# converter.net
KiCad netlist of a schematic drawn in EAGLE
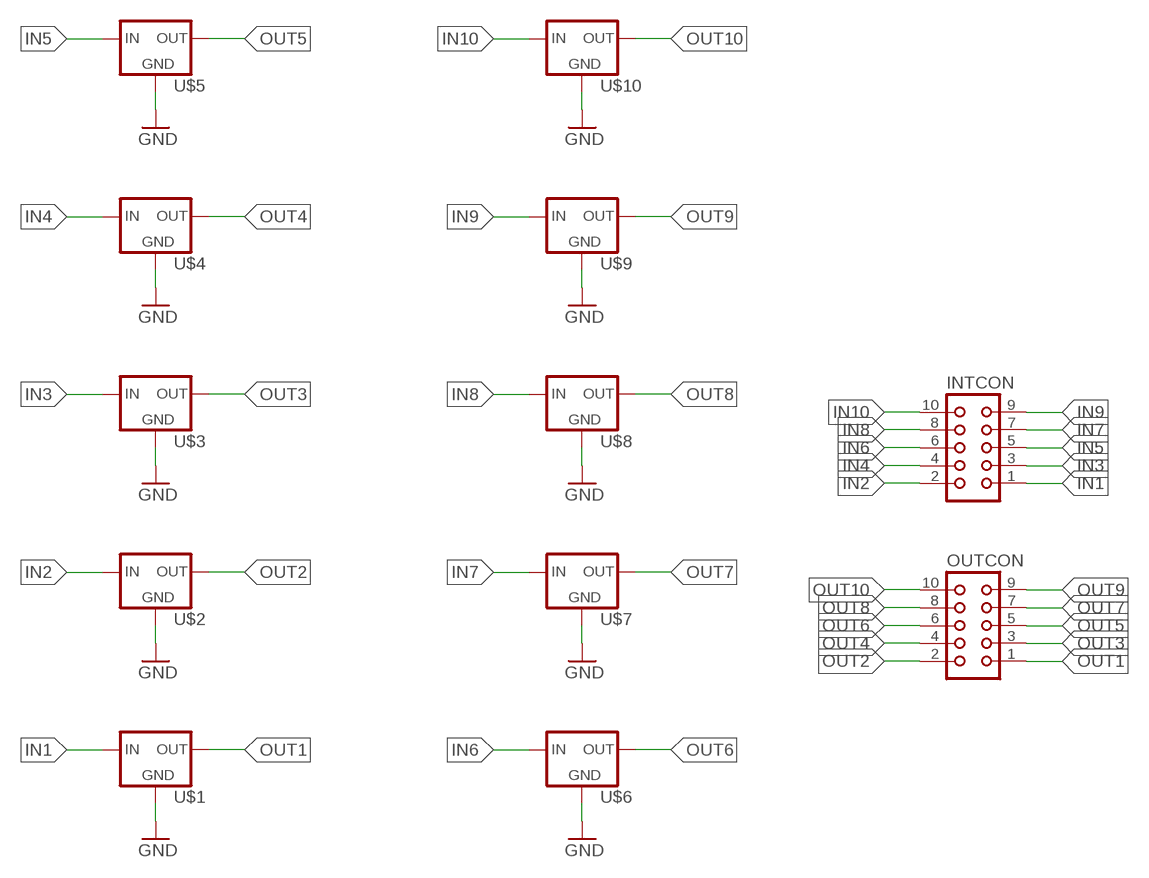
[diagram p0: schematic, sheet 1]

(export (version "E")
  (design (tool "Eeschema 10.0.6"))
  (components
    (comp (ref "INTCON")
      (value "CON10")
      (footprint "eagle-import:CON10")
      (libsource (lib "eagle-import") (part "CON10"))
    )
    (comp (ref "OUTCON")
      (value "CON10")
      (footprint "eagle-import:CON10")
      (libsource (lib "eagle-import") (part "CON10"))
    )
    (comp (ref "U$1")
      (value "LOGIC_CONVERTERIC")
      (footprint "eagle-import:SOT223")
      (libsource (lib "eagle-import") (part "LOGIC_CONVERTERIC"))
    )
    (comp (ref "U$2")
      (value "LOGIC_CONVERTERIC")
      (footprint "eagle-import:SOT223")
      (libsource (lib "eagle-import") (part "LOGIC_CONVERTERIC"))
    )
    (comp (ref "U$3")
      (value "LOGIC_CONVERTERIC")
      (footprint "eagle-import:SOT223")
      (libsource (lib "eagle-import") (part "LOGIC_CONVERTERIC"))
    )
    (comp (ref "U$4")
      (value "LOGIC_CONVERTERIC")
      (footprint "eagle-import:SOT223")
      (libsource (lib "eagle-import") (part "LOGIC_CONVERTERIC"))
    )
    (comp (ref "U$5")
      (value "LOGIC_CONVERTERIC")
      (footprint "eagle-import:SOT223")
      (libsource (lib "eagle-import") (part "LOGIC_CONVERTERIC"))
    )
    (comp (ref "U$6")
      (value "LOGIC_CONVERTERIC")
      (footprint "eagle-import:SOT223")
      (libsource (lib "eagle-import") (part "LOGIC_CONVERTERIC"))
    )
    (comp (ref "U$7")
      (value "LOGIC_CONVERTERIC")
      (footprint "eagle-import:SOT223")
      (libsource (lib "eagle-import") (part "LOGIC_CONVERTERIC"))
    )
    (comp (ref "U$8")
      (value "LOGIC_CONVERTERIC")
      (footprint "eagle-import:SOT223")
      (libsource (lib "eagle-import") (part "LOGIC_CONVERTERIC"))
    )
    (comp (ref "U$9")
      (value "LOGIC_CONVERTERIC")
      (footprint "eagle-import:SOT223")
      (libsource (lib "eagle-import") (part "LOGIC_CONVERTERIC"))
    )
    (comp (ref "U$10")
      (value "LOGIC_CONVERTERIC")
      (footprint "eagle-import:SOT223")
      (libsource (lib "eagle-import") (part "LOGIC_CONVERTERIC"))
    )
  )
  (nets
    (net (code "1") (name "GND") (class "Default")
      (node (ref "U$1") (pin "2") (pinfunction "GND_2") (pintype "input"))
      (node (ref "U$1") (pin "3") (pinfunction "GND_3") (pintype "input"))
      (node (ref "U$1") (pin "4") (pinfunction "GND_4") (pintype "input"))
      (node (ref "U$1") (pin "GND") (pinfunction "GND_GND") (pintype "input"))
      (node (ref "U$10") (pin "2") (pinfunction "GND_2") (pintype "input"))
      (node (ref "U$10") (pin "3") (pinfunction "GND_3") (pintype "input"))
      (node (ref "U$10") (pin "4") (pinfunction "GND_4") (pintype "input"))
      (node (ref "U$10") (pin "GND") (pinfunction "GND_GND") (pintype "input"))
      (node (ref "U$2") (pin "2") (pinfunction "GND_2") (pintype "input"))
      (node (ref "U$2") (pin "3") (pinfunction "GND_3") (pintype "input"))
      (node (ref "U$2") (pin "4") (pinfunction "GND_4") (pintype "input"))
      (node (ref "U$2") (pin "GND") (pinfunction "GND_GND") (pintype "input"))
      (node (ref "U$3") (pin "2") (pinfunction "GND_2") (pintype "input"))
      (node (ref "U$3") (pin "3") (pinfunction "GND_3") (pintype "input"))
      (node (ref "U$3") (pin "4") (pinfunction "GND_4") (pintype "input"))
      (node (ref "U$3") (pin "GND") (pinfunction "GND_GND") (pintype "input"))
      (node (ref "U$4") (pin "2") (pinfunction "GND_2") (pintype "input"))
      (node (ref "U$4") (pin "3") (pinfunction "GND_3") (pintype "input"))
      (node (ref "U$4") (pin "4") (pinfunction "GND_4") (pintype "input"))
      (node (ref "U$4") (pin "GND") (pinfunction "GND_GND") (pintype "input"))
      (node (ref "U$5") (pin "2") (pinfunction "GND_2") (pintype "input"))
      (node (ref "U$5") (pin "3") (pinfunction "GND_3") (pintype "input"))
      (node (ref "U$5") (pin "4") (pinfunction "GND_4") (pintype "input"))
      (node (ref "U$5") (pin "GND") (pinfunction "GND_GND") (pintype "input"))
      (node (ref "U$6") (pin "2") (pinfunction "GND_2") (pintype "input"))
      (node (ref "U$6") (pin "3") (pinfunction "GND_3") (pintype "input"))
      (node (ref "U$6") (pin "4") (pinfunction "GND_4") (pintype "input"))
      (node (ref "U$6") (pin "GND") (pinfunction "GND_GND") (pintype "input"))
      (node (ref "U$7") (pin "2") (pinfunction "GND_2") (pintype "input"))
      (node (ref "U$7") (pin "3") (pinfunction "GND_3") (pintype "input"))
      (node (ref "U$7") (pin "4") (pinfunction "GND_4") (pintype "input"))
      (node (ref "U$7") (pin "GND") (pinfunction "GND_GND") (pintype "input"))
      (node (ref "U$8") (pin "2") (pinfunction "GND_2") (pintype "input"))
      (node (ref "U$8") (pin "3") (pinfunction "GND_3") (pintype "input"))
      (node (ref "U$8") (pin "4") (pinfunction "GND_4") (pintype "input"))
      (node (ref "U$8") (pin "GND") (pinfunction "GND_GND") (pintype "input"))
      (node (ref "U$9") (pin "2") (pinfunction "GND_2") (pintype "input"))
      (node (ref "U$9") (pin "3") (pinfunction "GND_3") (pintype "input"))
      (node (ref "U$9") (pin "4") (pinfunction "GND_4") (pintype "input"))
      (node (ref "U$9") (pin "GND") (pinfunction "GND_GND") (pintype "input"))
    )
    (net (code "2") (name "IN1") (class "Default")
      (node (ref "INTCON") (pin "1") (pinfunction "1_1") (pintype "passive"))
      (node (ref "U$1") (pin "1") (pinfunction "IN_1") (pintype "input"))
      (node (ref "U$1") (pin "IN") (pinfunction "IN_IN") (pintype "input"))
    )
    (net (code "3") (name "IN2") (class "Default")
      (node (ref "INTCON") (pin "2") (pinfunction "2_2") (pintype "passive"))
      (node (ref "U$2") (pin "1") (pinfunction "IN_1") (pintype "input"))
      (node (ref "U$2") (pin "IN") (pinfunction "IN_IN") (pintype "input"))
    )
    (net (code "4") (name "IN3") (class "Default")
      (node (ref "INTCON") (pin "3") (pinfunction "3_3") (pintype "passive"))
      (node (ref "U$3") (pin "1") (pinfunction "IN_1") (pintype "input"))
      (node (ref "U$3") (pin "IN") (pinfunction "IN_IN") (pintype "input"))
    )
    (net (code "5") (name "IN4") (class "Default")
      (node (ref "INTCON") (pin "4") (pinfunction "4_4") (pintype "passive"))
      (node (ref "U$4") (pin "1") (pinfunction "IN_1") (pintype "input"))
      (node (ref "U$4") (pin "IN") (pinfunction "IN_IN") (pintype "input"))
    )
    (net (code "6") (name "IN5") (class "Default")
      (node (ref "INTCON") (pin "5") (pinfunction "5_5") (pintype "passive"))
      (node (ref "U$5") (pin "1") (pinfunction "IN_1") (pintype "input"))
      (node (ref "U$5") (pin "IN") (pinfunction "IN_IN") (pintype "input"))
    )
    (net (code "7") (name "IN6") (class "Default")
      (node (ref "INTCON") (pin "6") (pinfunction "6_6") (pintype "passive"))
      (node (ref "U$6") (pin "1") (pinfunction "IN_1") (pintype "input"))
      (node (ref "U$6") (pin "IN") (pinfunction "IN_IN") (pintype "input"))
    )
    (net (code "8") (name "IN7") (class "Default")
      (node (ref "INTCON") (pin "7") (pinfunction "7_7") (pintype "passive"))
      (node (ref "U$7") (pin "1") (pinfunction "IN_1") (pintype "input"))
      (node (ref "U$7") (pin "IN") (pinfunction "IN_IN") (pintype "input"))
    )
    (net (code "9") (name "IN8") (class "Default")
      (node (ref "INTCON") (pin "8") (pinfunction "8_8") (pintype "passive"))
      (node (ref "U$8") (pin "1") (pinfunction "IN_1") (pintype "input"))
      (node (ref "U$8") (pin "IN") (pinfunction "IN_IN") (pintype "input"))
    )
    (net (code "10") (name "IN9") (class "Default")
      (node (ref "INTCON") (pin "9") (pinfunction "9_9") (pintype "passive"))
      (node (ref "U$9") (pin "1") (pinfunction "IN_1") (pintype "input"))
      (node (ref "U$9") (pin "IN") (pinfunction "IN_IN") (pintype "input"))
    )
    (net (code "11") (name "IN10") (class "Default")
      (node (ref "INTCON") (pin "10") (pinfunction "10_10") (pintype "passive"))
      (node (ref "U$10") (pin "1") (pinfunction "IN_1") (pintype "input"))
      (node (ref "U$10") (pin "IN") (pinfunction "IN_IN") (pintype "input"))
    )
    (net (code "12") (name "OUT1") (class "Default")
      (node (ref "OUTCON") (pin "1") (pinfunction "1_1") (pintype "passive"))
      (node (ref "U$1") (pin "5") (pinfunction "OUT_5") (pintype "passive"))
      (node (ref "U$1") (pin "OUT") (pinfunction "OUT_OUT") (pintype "passive"))
    )
    (net (code "13") (name "OUT2") (class "Default")
      (node (ref "OUTCON") (pin "2") (pinfunction "2_2") (pintype "passive"))
      (node (ref "U$2") (pin "5") (pinfunction "OUT_5") (pintype "passive"))
      (node (ref "U$2") (pin "OUT") (pinfunction "OUT_OUT") (pintype "passive"))
    )
    (net (code "14") (name "OUT3") (class "Default")
      (node (ref "OUTCON") (pin "3") (pinfunction "3_3") (pintype "passive"))
      (node (ref "U$3") (pin "5") (pinfunction "OUT_5") (pintype "passive"))
      (node (ref "U$3") (pin "OUT") (pinfunction "OUT_OUT") (pintype "passive"))
    )
    (net (code "15") (name "OUT4") (class "Default")
      (node (ref "OUTCON") (pin "4") (pinfunction "4_4") (pintype "passive"))
      (node (ref "U$4") (pin "5") (pinfunction "OUT_5") (pintype "passive"))
      (node (ref "U$4") (pin "OUT") (pinfunction "OUT_OUT") (pintype "passive"))
    )
    (net (code "16") (name "OUT5") (class "Default")
      (node (ref "OUTCON") (pin "5") (pinfunction "5_5") (pintype "passive"))
      (node (ref "U$5") (pin "5") (pinfunction "OUT_5") (pintype "passive"))
      (node (ref "U$5") (pin "OUT") (pinfunction "OUT_OUT") (pintype "passive"))
    )
    (net (code "17") (name "OUT6") (class "Default")
      (node (ref "OUTCON") (pin "6") (pinfunction "6_6") (pintype "passive"))
      (node (ref "U$6") (pin "5") (pinfunction "OUT_5") (pintype "passive"))
      (node (ref "U$6") (pin "OUT") (pinfunction "OUT_OUT") (pintype "passive"))
    )
    (net (code "18") (name "OUT7") (class "Default")
      (node (ref "OUTCON") (pin "7") (pinfunction "7_7") (pintype "passive"))
      (node (ref "U$7") (pin "5") (pinfunction "OUT_5") (pintype "passive"))
      (node (ref "U$7") (pin "OUT") (pinfunction "OUT_OUT") (pintype "passive"))
    )
    (net (code "19") (name "OUT8") (class "Default")
      (node (ref "OUTCON") (pin "8") (pinfunction "8_8") (pintype "passive"))
      (node (ref "U$8") (pin "5") (pinfunction "OUT_5") (pintype "passive"))
      (node (ref "U$8") (pin "OUT") (pinfunction "OUT_OUT") (pintype "passive"))
    )
    (net (code "20") (name "OUT9") (class "Default")
      (node (ref "OUTCON") (pin "9") (pinfunction "9_9") (pintype "passive"))
      (node (ref "U$9") (pin "5") (pinfunction "OUT_5") (pintype "passive"))
      (node (ref "U$9") (pin "OUT") (pinfunction "OUT_OUT") (pintype "passive"))
    )
    (net (code "21") (name "OUT10") (class "Default")
      (node (ref "OUTCON") (pin "10") (pinfunction "10_10") (pintype "passive"))
      (node (ref "U$10") (pin "5") (pinfunction "OUT_5") (pintype "passive"))
      (node (ref "U$10") (pin "OUT") (pinfunction "OUT_OUT") (pintype "passive"))
    )
  )
)
